# Sheet1.net
KiCad netlist of a schematic drawn in Altium Designer
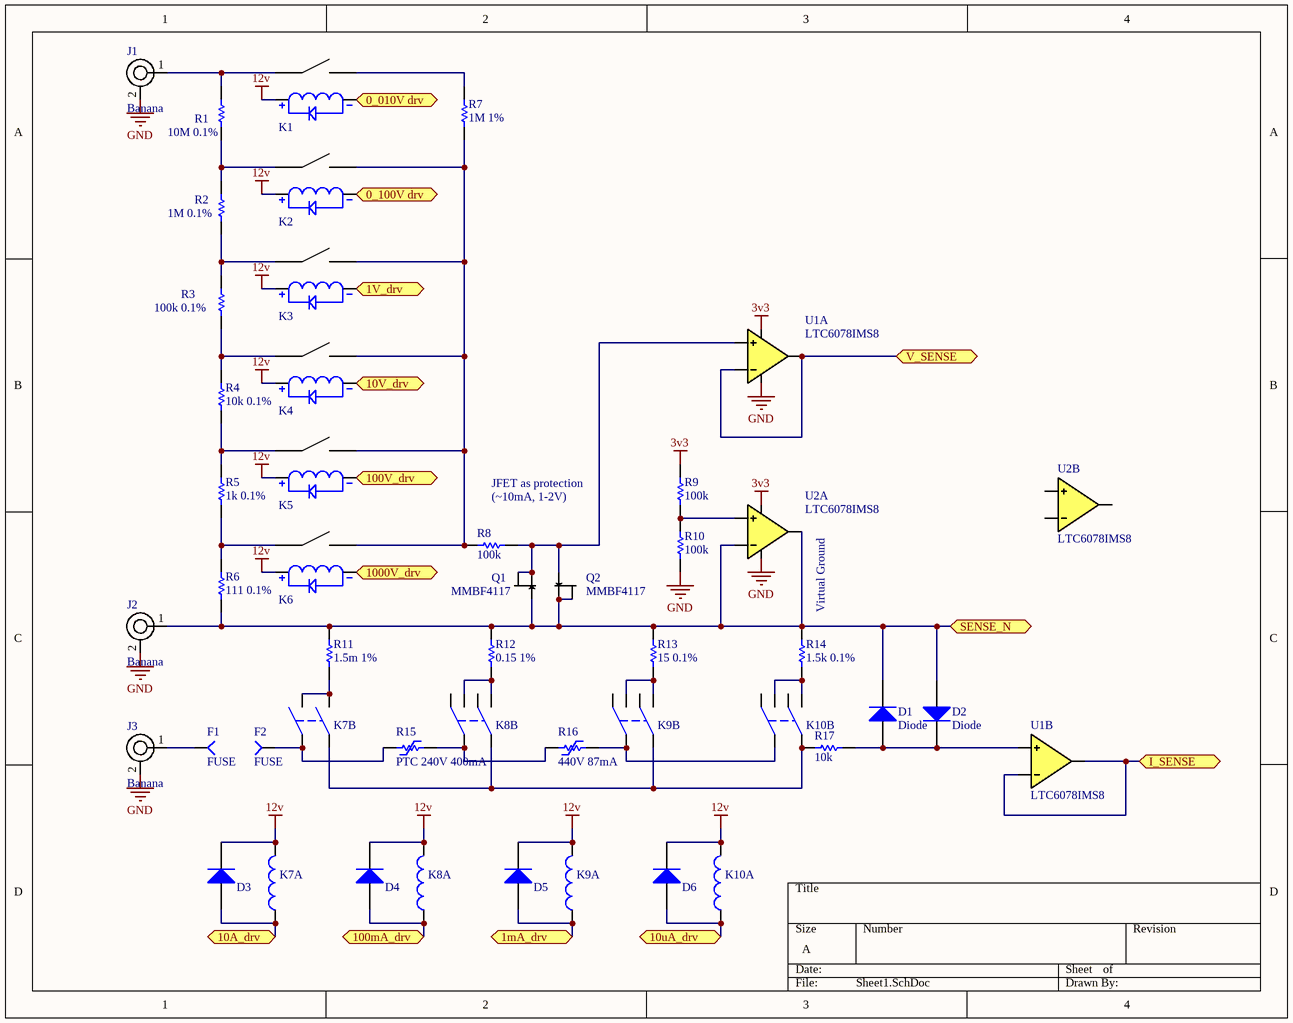
[diagram p0: Sheet1.SchDoc]

(export (version "E")
  (design (tool "Eeschema 10.0.6"))
  (components
    (comp (ref "D1")
      (value "Diode")
      (footprint "SOD80")
      (description "DIODE GEN PURP 125V 200MA LL34")
      (libsource (lib "Schlib1") (part "Diode 125V 200mA"))
    )
    (comp (ref "D2")
      (value "Diode")
      (footprint "SOD80")
      (description "DIODE GEN PURP 125V 200MA LL34")
      (libsource (lib "Schlib1") (part "Diode 125V 200mA"))
    )
    (comp (ref "D3")
      (value "Diode")
      (footprint "SOD80")
      (description "DIODE GEN PURP 100V 200MA LL34")
      (libsource (lib "Schlib1") (part "Diode 100V 200mA"))
    )
    (comp (ref "D4")
      (value "Diode")
      (footprint "SOD80")
      (description "DIODE GEN PURP 100V 200MA LL34")
      (libsource (lib "Schlib1") (part "Diode 100V 200mA"))
    )
    (comp (ref "D5")
      (value "Diode")
      (footprint "SOD80")
      (description "DIODE GEN PURP 100V 200MA LL34")
      (libsource (lib "Schlib1") (part "Diode 100V 200mA"))
    )
    (comp (ref "D6")
      (value "Diode")
      (footprint "SOD80")
      (description "DIODE GEN PURP 100V 200MA LL34")
      (libsource (lib "Schlib1") (part "Diode 100V 200mA"))
    )
    (comp (ref "F1")
      (value "FUSE")
      (footprint "FUSE CLIP")
      (description "FUSE CLIP CARTRIDGE 30A PCB")
      (libsource (lib "Schlib1") (part "FUSE CLIP"))
    )
    (comp (ref "F2")
      (value "FUSE")
      (footprint "FUSE CLIP")
      (description "FUSE CLIP CARTRIDGE 30A PCB")
      (libsource (lib "Schlib1") (part "FUSE CLIP"))
    )
    (comp (ref "J1")
      (value "Banana")
      (footprint "FCR7350")
      (description "SOCKET, PCB, 4MM, R/A, S16N-PC, YEL")
      (libsource (lib "Schlib1") (part "Banana Jack"))
    )
    (comp (ref "J2")
      (value "Banana")
      (footprint "FCR7350")
      (description "SOCKET, PCB, 4MM, R/A, S16N-PC, YEL")
      (libsource (lib "Schlib1") (part "Banana Jack"))
    )
    (comp (ref "J3")
      (value "Banana")
      (footprint "FCR7350")
      (description "SOCKET, PCB, 4MM, R/A, S16N-PC, YEL")
      (libsource (lib "Schlib1") (part "Banana Jack"))
    )
    (comp (ref "K1")
      (value "Relay Reed SPST 1000V / 500mA 12V")
      (footprint "Coto 9104-12-11")
      (description "RELAY REED SPST 500MA 12V")
      (libsource (lib "Schlib1") (part "Relay Reed SPST 1000V / 500mA 12V"))
    )
    (comp (ref "K2")
      (value "Relay Reed SPST 500mA 12V")
      (footprint "HE3621A")
      (description "RELAY REED SPST 500MA 12V")
      (libsource (lib "Schlib1") (part "Relay Reed SPST 500mA 12V"))
    )
    (comp (ref "K3")
      (value "Relay Reed SPST 500mA 12V")
      (footprint "HE3621A")
      (description "RELAY REED SPST 500MA 12V")
      (libsource (lib "Schlib1") (part "Relay Reed SPST 500mA 12V"))
    )
    (comp (ref "K4")
      (value "Relay Reed SPST 500mA 12V")
      (footprint "HE3621A")
      (description "RELAY REED SPST 500MA 12V")
      (libsource (lib "Schlib1") (part "Relay Reed SPST 500mA 12V"))
    )
    (comp (ref "K5")
      (value "Relay Reed SPST 500mA 12V")
      (footprint "HE3621A")
      (description "RELAY REED SPST 500MA 12V")
      (libsource (lib "Schlib1") (part "Relay Reed SPST 500mA 12V"))
    )
    (comp (ref "K6")
      (value "Relay Reed SPST 500mA 12V")
      (footprint "HE3621A")
      (description "RELAY REED SPST 500MA 12V")
      (libsource (lib "Schlib1") (part "Relay Reed SPST 500mA 12V"))
    )
    (comp (ref "K7")
      (value "Relay DPST 15A 12V")
      (footprint "G4W-2212P-US-TV5")
      (description "RELAY GEN PURPOSE DPST 15A 12V")
      (libsource (lib "Schlib1") (part "Relay DPST 15A 12V"))
    )
    (comp (ref "K8")
      (value "Relay DPDT 2A 12V")
      (footprint "EE2-12NU")
      (description "RELAY GEN PURPOSE DPDT 2A 12V")
      (libsource (lib "Schlib1") (part "Relay DPDT 2A 12V"))
    )
    (comp (ref "K9")
      (value "Relay DPDT 2A 12V")
      (footprint "EE2-12NU")
      (description "RELAY GEN PURPOSE DPDT 2A 12V")
      (libsource (lib "Schlib1") (part "Relay DPDT 2A 12V"))
    )
    (comp (ref "K10")
      (value "Relay DPDT 2A 12V")
      (footprint "EE2-12NU")
      (description "RELAY GEN PURPOSE DPDT 2A 12V")
      (libsource (lib "Schlib1") (part "Relay DPDT 2A 12V"))
    )
    (comp (ref "Q1")
      (value "MMBF4117")
      (footprint "SOT_23")
      (description "JFET N-CH 40V 0.225W SOT23")
      (libsource (lib "Schlib1") (part "MMBF4117"))
    )
    (comp (ref "Q2")
      (value "MMBF4117")
      (footprint "SOT_23")
      (description "JFET N-CH 40V 0.225W SOT23")
      (libsource (lib "Schlib1") (part "MMBF4117"))
    )
    (comp (ref "R1")
      (value "10M 0.1%")
      (footprint "R2010")
      (description "RES SMD 10M OHM 0.1% 1W 2010")
      (libsource (lib "Schlib1") (part "10M 2010 0.1%"))
    )
    (comp (ref "R2")
      (value "1M 0.1%")
      (footprint "R1206")
      (description "RES SMD 1M OHM 0.1% 1/4W 1206")
      (libsource (lib "Schlib1") (part "1M 1206 0.1%"))
    )
    (comp (ref "R3")
      (value "100k 0.1%")
      (footprint "R0805")
      (description "RES SMD 100K OHM 0.1% 1/8W 0805")
      (libsource (lib "Schlib1") (part "100k 0805 0.1%"))
    )
    (comp (ref "R4")
      (value "10k 0.1%")
      (footprint "R0603")
      (description "RES SMD 10K OHM 0.1% 1/10W 0603")
      (libsource (lib "Schlib1") (part "10k 0603 0.1%"))
    )
    (comp (ref "R5")
      (value "1k 0.1%")
      (footprint "R0603")
      (description "RES SMD 1K OHM 0.1% 1/10W 0603")
      (libsource (lib "Schlib1") (part "1k 0603 0.1%"))
    )
    (comp (ref "R6")
      (value "111 0.1%")
      (footprint "R0402")
      (description "RES 111 OHM 0.1% 1/10W 0402")
      (libsource (lib "Schlib1") (part "111 0402 0.1%"))
    )
    (comp (ref "R7")
      (value "1M 1%")
      (footprint "R2512")
      (description "CHV2512-FX-1004ELF")
      (libsource (lib "Schlib1") (part "1M 2512 1%"))
    )
    (comp (ref "R8")
      (value "100k")
      (footprint "R0603")
      (description "RES SMD 100K OHM 5% 1/10W 0603")
      (libsource (lib "Schlib1") (part "100k 0603 5%"))
    )
    (comp (ref "R9")
      (value "100k")
      (footprint "R0603")
      (description "RES SMD 100K OHM 5% 1/10W 0603")
      (libsource (lib "Schlib1") (part "100k 0603 5%"))
    )
    (comp (ref "R10")
      (value "100k")
      (footprint "R0603")
      (description "RES SMD 100K OHM 5% 1/10W 0603")
      (libsource (lib "Schlib1") (part "100k 0603 5%"))
    )
    (comp (ref "R11")
      (value "1.5m 1%")
      (footprint "R2512")
      (description "RES 0.0015 OHM 1% 3W 2512")
      (libsource (lib "Schlib1") (part "1.5m 2512 1%"))
    )
    (comp (ref "R12")
      (value "0.15 1%")
      (footprint "R2010")
      (description "RES 0.15 OHM 1% 1W 2010")
      (libsource (lib "Schlib1") (part "0.15 2010 1%"))
    )
    (comp (ref "R13")
      (value "15 0.1%")
      (footprint "R0805")
      (description "RES SMD 15 OHM 0.1% 1/8W 0805")
      (libsource (lib "Schlib1") (part "15 0805 0.1%"))
    )
    (comp (ref "R14")
      (value "1.5k 0.1%")
      (footprint "R0603")
      (description "RES SMD 1.5K OHM 0.1% 1/5W 0603")
      (libsource (lib "Schlib1") (part "1.5k 0603 0.1%"))
    )
    (comp (ref "R15")
      (value "PTC 240V 400mA")
      (footprint "0ZRE0040FF1A")
      (description "PTC RESET FUSE 240V 400MA RADIAL")
      (libsource (lib "Schlib1") (part "PTC 240V 400mA"))
    )
    (comp (ref "R16")
      (value "440V 87mA")
      (footprint "B59751C0120A070")
      (description "PTC RESET FUSE 440V 87MA RADIAL")
      (libsource (lib "Schlib1") (part "PTC 440V 87mA"))
    )
    (comp (ref "R17")
      (value "10k")
      (footprint "R0603")
      (description "RES SMD 10K OHM 5% 1/10W 0603")
      (libsource (lib "Schlib1") (part "10k 0603 5%"))
    )
    (comp (ref "U1") (value "LTC6078IMS8") (libsource (lib "Schlib1") (part "LTC6078IMS8")))
    (comp (ref "U2") (value "LTC6078IMS8") (libsource (lib "Schlib1") (part "LTC6078IMS8")))
  )
  (nets
    (net (code "1") (name "/0_010V drv") (class "Default")
      (node (ref "K1") (pin "5") (pinfunction "5_5") (pintype "passive"))
    )
    (net (code "2") (name "/0_100V drv") (class "Default")
      (node (ref "K2") (pin "3") (pinfunction "3_3") (pintype "passive"))
    )
    (net (code "3") (name "/1V_drv") (class "Default")
      (node (ref "K3") (pin "3") (pinfunction "3_3") (pintype "passive"))
    )
    (net (code "4") (name "/1mA_drv") (class "Default")
      (node (ref "D5") (pin "1") (pinfunction "A_1") (pintype "passive"))
      (node (ref "K9") (pin "1") (pinfunction "1_1") (pintype "passive"))
    )
    (net (code "5") (name "/10A_drv") (class "Default")
      (node (ref "D3") (pin "1") (pinfunction "A_1") (pintype "passive"))
      (node (ref "K7") (pin "5") (pinfunction "5_5") (pintype "passive"))
    )
    (net (code "6") (name "/10V_drv") (class "Default")
      (node (ref "K4") (pin "3") (pinfunction "3_3") (pintype "passive"))
    )
    (net (code "7") (name "/10uA_drv") (class "Default")
      (node (ref "D6") (pin "1") (pinfunction "A_1") (pintype "passive"))
      (node (ref "K10") (pin "1") (pinfunction "1_1") (pintype "passive"))
    )
    (net (code "8") (name "/100V_drv") (class "Default")
      (node (ref "K5") (pin "3") (pinfunction "3_3") (pintype "passive"))
    )
    (net (code "9") (name "/100mA_drv") (class "Default")
      (node (ref "D4") (pin "1") (pinfunction "A_1") (pintype "passive"))
      (node (ref "K8") (pin "1") (pinfunction "1_1") (pintype "passive"))
    )
    (net (code "10") (name "/1000V_drv") (class "Default")
      (node (ref "K6") (pin "3") (pinfunction "3_3") (pintype "passive"))
    )
    (net (code "11") (name "/I_SENSE") (class "Default")
      (node (ref "U1") (pin "6") (pinfunction "6_6") (pintype "passive"))
      (node (ref "U1") (pin "7") (pinfunction "7_7") (pintype "passive"))
    )
    (net (code "12") (name "/SENSE_N") (class "Default")
      (node (ref "D1") (pin "2") (pinfunction "K_2") (pintype "passive"))
      (node (ref "D2") (pin "1") (pinfunction "A_1") (pintype "passive"))
      (node (ref "J2") (pin "1") (pinfunction "1_1") (pintype "passive"))
      (node (ref "Q1") (pin "3") (pinfunction "3_3") (pintype "passive"))
      (node (ref "Q2") (pin "1") (pinfunction "1_1") (pintype "passive"))
      (node (ref "Q2") (pin "2") (pinfunction "2_2") (pintype "passive"))
      (node (ref "R11") (pin "2") (pinfunction "2_2") (pintype "passive"))
      (node (ref "R12") (pin "2") (pinfunction "2_2") (pintype "passive"))
      (node (ref "R13") (pin "2") (pinfunction "2_2") (pintype "passive"))
      (node (ref "R14") (pin "2") (pinfunction "2_2") (pintype "passive"))
      (node (ref "R6") (pin "1") (pinfunction "1_1") (pintype "passive"))
      (node (ref "U2") (pin "1") (pinfunction "1_1") (pintype "passive"))
      (node (ref "U2") (pin "2") (pinfunction "2_2") (pintype "passive"))
    )
    (net (code "13") (name "/V_SENSE") (class "Default")
      (node (ref "U1") (pin "1") (pinfunction "1_1") (pintype "passive"))
      (node (ref "U1") (pin "2") (pinfunction "2_2") (pintype "passive"))
    )
    (net (code "14") (name "3v3") (class "Default")
      (node (ref "R9") (pin "2") (pinfunction "2_2") (pintype "passive"))
      (node (ref "U1") (pin "8") (pinfunction "8_8") (pintype "passive"))
      (node (ref "U2") (pin "8") (pinfunction "8_8") (pintype "passive"))
    )
    (net (code "15") (name "12v") (class "Default")
      (node (ref "D3") (pin "2") (pinfunction "K_2") (pintype "passive"))
      (node (ref "D4") (pin "2") (pinfunction "K_2") (pintype "passive"))
      (node (ref "D5") (pin "2") (pinfunction "K_2") (pintype "passive"))
      (node (ref "D6") (pin "2") (pinfunction "K_2") (pintype "passive"))
      (node (ref "K1") (pin "3") (pinfunction "3_3") (pintype "passive"))
      (node (ref "K10") (pin "12") (pinfunction "12_12") (pintype "passive"))
      (node (ref "K2") (pin "2") (pinfunction "2_2") (pintype "passive"))
      (node (ref "K3") (pin "2") (pinfunction "2_2") (pintype "passive"))
      (node (ref "K4") (pin "2") (pinfunction "2_2") (pintype "passive"))
      (node (ref "K5") (pin "2") (pinfunction "2_2") (pintype "passive"))
      (node (ref "K6") (pin "2") (pinfunction "2_2") (pintype "passive"))
      (node (ref "K7") (pin "6") (pinfunction "6_6") (pintype "passive"))
      (node (ref "K8") (pin "12") (pinfunction "12_12") (pintype "passive"))
      (node (ref "K9") (pin "12") (pinfunction "12_12") (pintype "passive"))
    )
    (net (code "16") (name "GND") (class "Default")
      (node (ref "J1") (pin "2") (pinfunction "2_2") (pintype "passive"))
      (node (ref "J2") (pin "2") (pinfunction "2_2") (pintype "passive"))
      (node (ref "J3") (pin "2") (pinfunction "2_2") (pintype "passive"))
      (node (ref "R10") (pin "1") (pinfunction "1_1") (pintype "passive"))
      (node (ref "U1") (pin "4") (pinfunction "4_4") (pintype "passive"))
      (node (ref "U2") (pin "4") (pinfunction "4_4") (pintype "passive"))
    )
    (net (code "17") (name "Net-(D1-A)") (class "Default")
      (node (ref "D1") (pin "1") (pinfunction "A_1") (pintype "passive"))
      (node (ref "D2") (pin "2") (pinfunction "K_2") (pintype "passive"))
      (node (ref "R17") (pin "2") (pinfunction "2_2") (pintype "passive"))
      (node (ref "U1") (pin "5") (pinfunction "5_5") (pintype "passive"))
    )
    (net (code "18") (name "Net-(F1-Pad1)") (class "Default")
      (node (ref "F1") (pin "1") (pinfunction "1_1") (pintype "passive"))
      (node (ref "J3") (pin "1") (pinfunction "1_1") (pintype "passive"))
    )
    (net (code "19") (name "Net-(F2-Pad1)") (class "Default")
      (node (ref "F2") (pin "1") (pinfunction "1_1") (pintype "passive"))
      (node (ref "K7") (pin "2") (pinfunction "2_2") (pintype "passive"))
      (node (ref "R15") (pin "1") (pinfunction "1_1") (pintype "passive"))
    )
    (net (code "20") (name "Net-(J1-Pad1)") (class "Default")
      (node (ref "J1") (pin "1") (pinfunction "1_1") (pintype "passive"))
      (node (ref "K1") (pin "1") (pinfunction "1_1") (pintype "passive"))
      (node (ref "R1") (pin "2") (pinfunction "2_2") (pintype "passive"))
    )
    (net (code "21") (name "Net-(K1-Pad7)") (class "Default")
      (node (ref "K1") (pin "7") (pinfunction "7_7") (pintype "passive"))
      (node (ref "R7") (pin "2") (pinfunction "2_2") (pintype "passive"))
    )
    (net (code "22") (name "Net-(K2-Pad1)") (class "Default")
      (node (ref "K2") (pin "1") (pinfunction "1_1") (pintype "passive"))
      (node (ref "R1") (pin "1") (pinfunction "1_1") (pintype "passive"))
      (node (ref "R2") (pin "2") (pinfunction "2_2") (pintype "passive"))
    )
    (net (code "23") (name "Net-(K2-Pad4)") (class "Default")
      (node (ref "K2") (pin "4") (pinfunction "4_4") (pintype "passive"))
      (node (ref "K3") (pin "4") (pinfunction "4_4") (pintype "passive"))
      (node (ref "K4") (pin "4") (pinfunction "4_4") (pintype "passive"))
      (node (ref "K5") (pin "4") (pinfunction "4_4") (pintype "passive"))
      (node (ref "K6") (pin "4") (pinfunction "4_4") (pintype "passive"))
      (node (ref "R7") (pin "1") (pinfunction "1_1") (pintype "passive"))
      (node (ref "R8") (pin "1") (pinfunction "1_1") (pintype "passive"))
    )
    (net (code "24") (name "Net-(K3-Pad1)") (class "Default")
      (node (ref "K3") (pin "1") (pinfunction "1_1") (pintype "passive"))
      (node (ref "R2") (pin "1") (pinfunction "1_1") (pintype "passive"))
      (node (ref "R3") (pin "2") (pinfunction "2_2") (pintype "passive"))
    )
    (net (code "25") (name "Net-(K4-Pad1)") (class "Default")
      (node (ref "K4") (pin "1") (pinfunction "1_1") (pintype "passive"))
      (node (ref "R3") (pin "1") (pinfunction "1_1") (pintype "passive"))
      (node (ref "R4") (pin "2") (pinfunction "2_2") (pintype "passive"))
    )
    (net (code "26") (name "Net-(K5-Pad1)") (class "Default")
      (node (ref "K5") (pin "1") (pinfunction "1_1") (pintype "passive"))
      (node (ref "R4") (pin "1") (pinfunction "1_1") (pintype "passive"))
      (node (ref "R5") (pin "2") (pinfunction "2_2") (pintype "passive"))
    )
    (net (code "27") (name "Net-(K6-Pad1)") (class "Default")
      (node (ref "K6") (pin "1") (pinfunction "1_1") (pintype "passive"))
      (node (ref "R5") (pin "1") (pinfunction "1_1") (pintype "passive"))
      (node (ref "R6") (pin "2") (pinfunction "2_2") (pintype "passive"))
    )
    (net (code "28") (name "Net-(K7-Pad3)") (class "Default")
      (node (ref "K7") (pin "3") (pinfunction "3_3") (pintype "passive"))
      (node (ref "K7") (pin "4") (pinfunction "4_4") (pintype "passive"))
      (node (ref "R11") (pin "1") (pinfunction "1_1") (pintype "passive"))
    )
    (net (code "29") (name "Net-(K8-Pad4)") (class "Default")
      (node (ref "K8") (pin "4") (pinfunction "4_4") (pintype "passive"))
      (node (ref "R15") (pin "2") (pinfunction "2_2") (pintype "passive"))
      (node (ref "R16") (pin "1") (pinfunction "1_1") (pintype "passive"))
    )
    (net (code "30") (name "Net-(K8-Pad5)") (class "Default")
      (node (ref "K8") (pin "5") (pinfunction "5_5") (pintype "passive"))
      (node (ref "K8") (pin "8") (pinfunction "8_8") (pintype "passive"))
      (node (ref "R12") (pin "1") (pinfunction "1_1") (pintype "passive"))
    )
    (net (code "31") (name "Net-(K9-Pad5)") (class "Default")
      (node (ref "K9") (pin "5") (pinfunction "5_5") (pintype "passive"))
      (node (ref "K9") (pin "8") (pinfunction "8_8") (pintype "passive"))
      (node (ref "R13") (pin "1") (pinfunction "1_1") (pintype "passive"))
    )
    (net (code "32") (name "Net-(K10-Pad4)") (class "Default")
      (node (ref "K10") (pin "4") (pinfunction "4_4") (pintype "passive"))
      (node (ref "K9") (pin "4") (pinfunction "4_4") (pintype "passive"))
      (node (ref "R16") (pin "2") (pinfunction "2_2") (pintype "passive"))
    )
    (net (code "33") (name "Net-(K10-Pad5)") (class "Default")
      (node (ref "K10") (pin "5") (pinfunction "5_5") (pintype "passive"))
      (node (ref "K10") (pin "8") (pinfunction "8_8") (pintype "passive"))
      (node (ref "R14") (pin "1") (pinfunction "1_1") (pintype "passive"))
    )
    (net (code "34") (name "Net-(K10-Pad9)") (class "Default")
      (node (ref "K10") (pin "9") (pinfunction "9_9") (pintype "passive"))
      (node (ref "K7") (pin "1") (pinfunction "1_1") (pintype "passive"))
      (node (ref "K8") (pin "9") (pinfunction "9_9") (pintype "passive"))
      (node (ref "K9") (pin "9") (pinfunction "9_9") (pintype "passive"))
      (node (ref "R17") (pin "1") (pinfunction "1_1") (pintype "passive"))
    )
    (net (code "35") (name "Net-(Q1-Pad1)") (class "Default")
      (node (ref "Q1") (pin "1") (pinfunction "1_1") (pintype "passive"))
      (node (ref "Q1") (pin "2") (pinfunction "2_2") (pintype "passive"))
      (node (ref "Q2") (pin "3") (pinfunction "3_3") (pintype "passive"))
      (node (ref "R8") (pin "2") (pinfunction "2_2") (pintype "passive"))
      (node (ref "U1") (pin "3") (pinfunction "3_3") (pintype "passive"))
    )
    (net (code "36") (name "Net-(R10-Pad2)") (class "Default")
      (node (ref "R10") (pin "2") (pinfunction "2_2") (pintype "passive"))
      (node (ref "R9") (pin "1") (pinfunction "1_1") (pintype "passive"))
      (node (ref "U2") (pin "3") (pinfunction "3_3") (pintype "passive"))
    )
    (net (code "37") (name "unconnected-(K8-Pad3)") (class "Default")
      (node (ref "K8") (pin "3") (pinfunction "3_3") (pintype "passive"))
    )
    (net (code "38") (name "unconnected-(K8-Pad10)") (class "Default")
      (node (ref "K8") (pin "10") (pinfunction "10_10") (pintype "passive"))
    )
    (net (code "39") (name "unconnected-(K9-Pad3)") (class "Default")
      (node (ref "K9") (pin "3") (pinfunction "3_3") (pintype "passive"))
    )
    (net (code "40") (name "unconnected-(K9-Pad10)") (class "Default")
      (node (ref "K9") (pin "10") (pinfunction "10_10") (pintype "passive"))
    )
    (net (code "41") (name "unconnected-(K10-Pad3)") (class "Default")
      (node (ref "K10") (pin "3") (pinfunction "3_3") (pintype "passive"))
    )
    (net (code "42") (name "unconnected-(K10-Pad10)") (class "Default")
      (node (ref "K10") (pin "10") (pinfunction "10_10") (pintype "passive"))
    )
    (net (code "43") (name "unconnected-(U2-Pad5)") (class "Default")
      (node (ref "U2") (pin "5") (pinfunction "5_5") (pintype "passive"))
    )
    (net (code "44") (name "unconnected-(U2-Pad6)") (class "Default")
      (node (ref "U2") (pin "6") (pinfunction "6_6") (pintype "passive"))
    )
    (net (code "45") (name "unconnected-(U2-Pad7)") (class "Default")
      (node (ref "U2") (pin "7") (pinfunction "7_7") (pintype "passive"))
    )
  )
)
